# zloshnik2.net
KiCad netlist of a schematic drawn in EAGLE
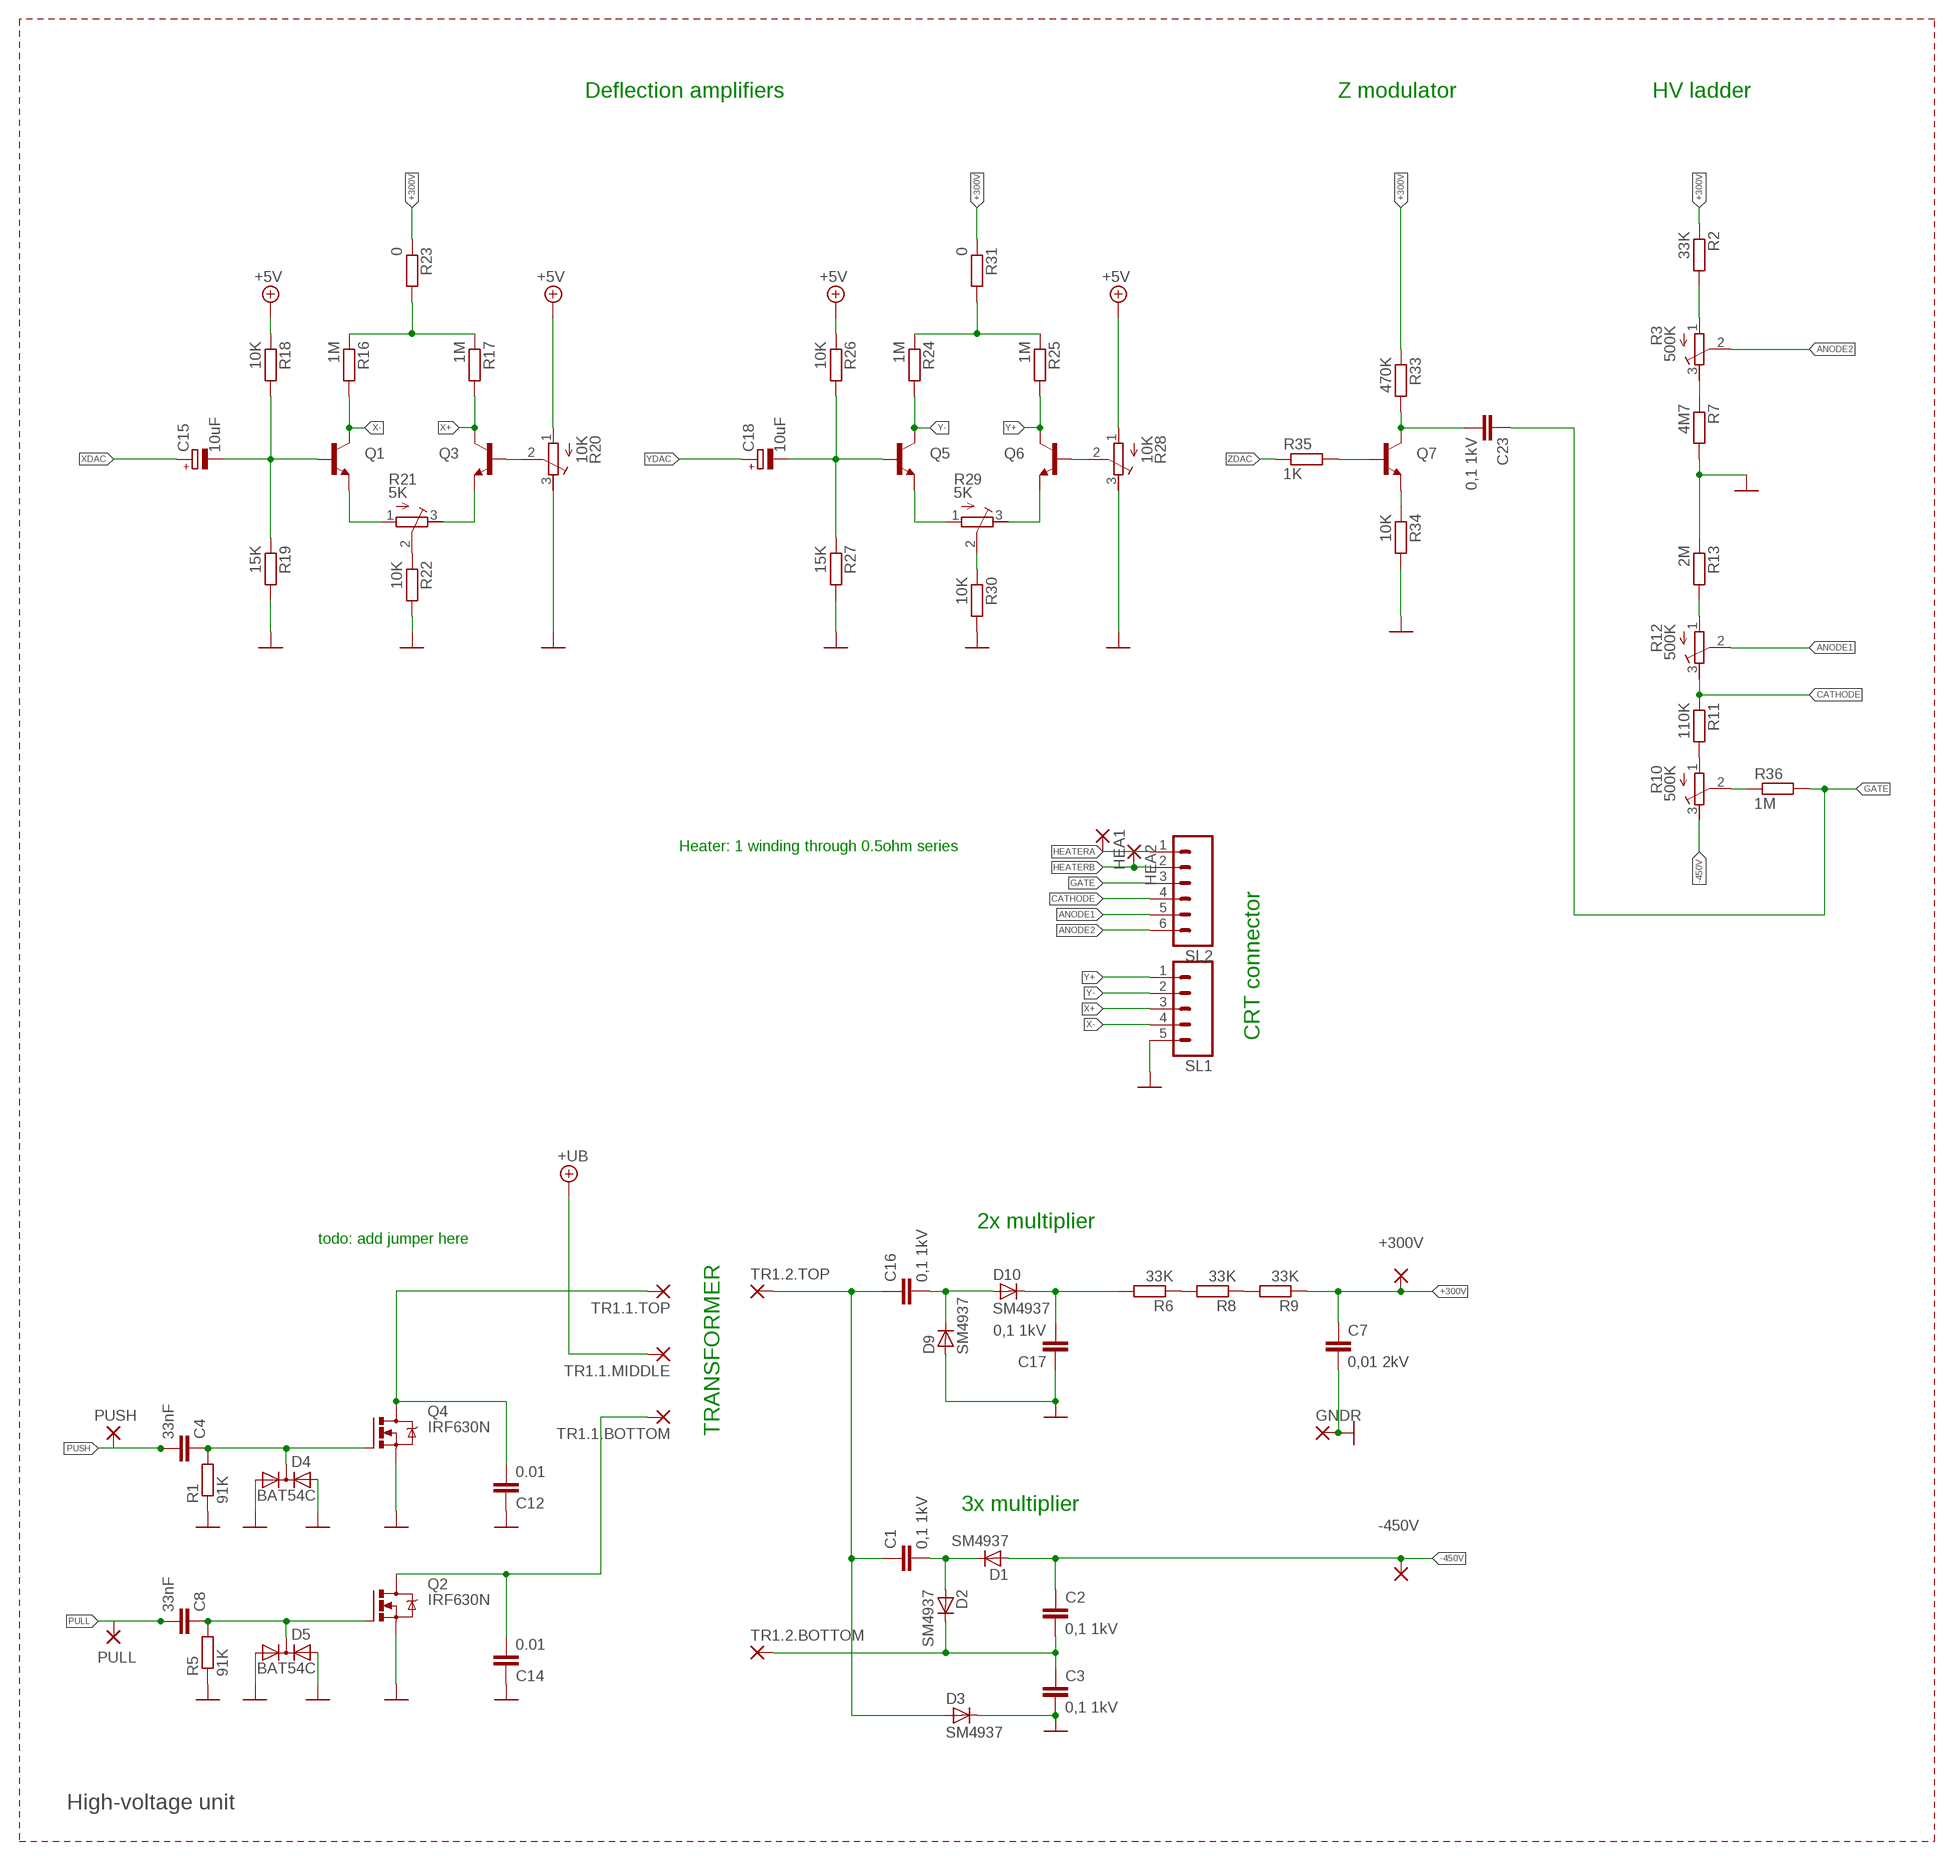
[diagram p0: schematic, sheet 1, part 1 of 2]
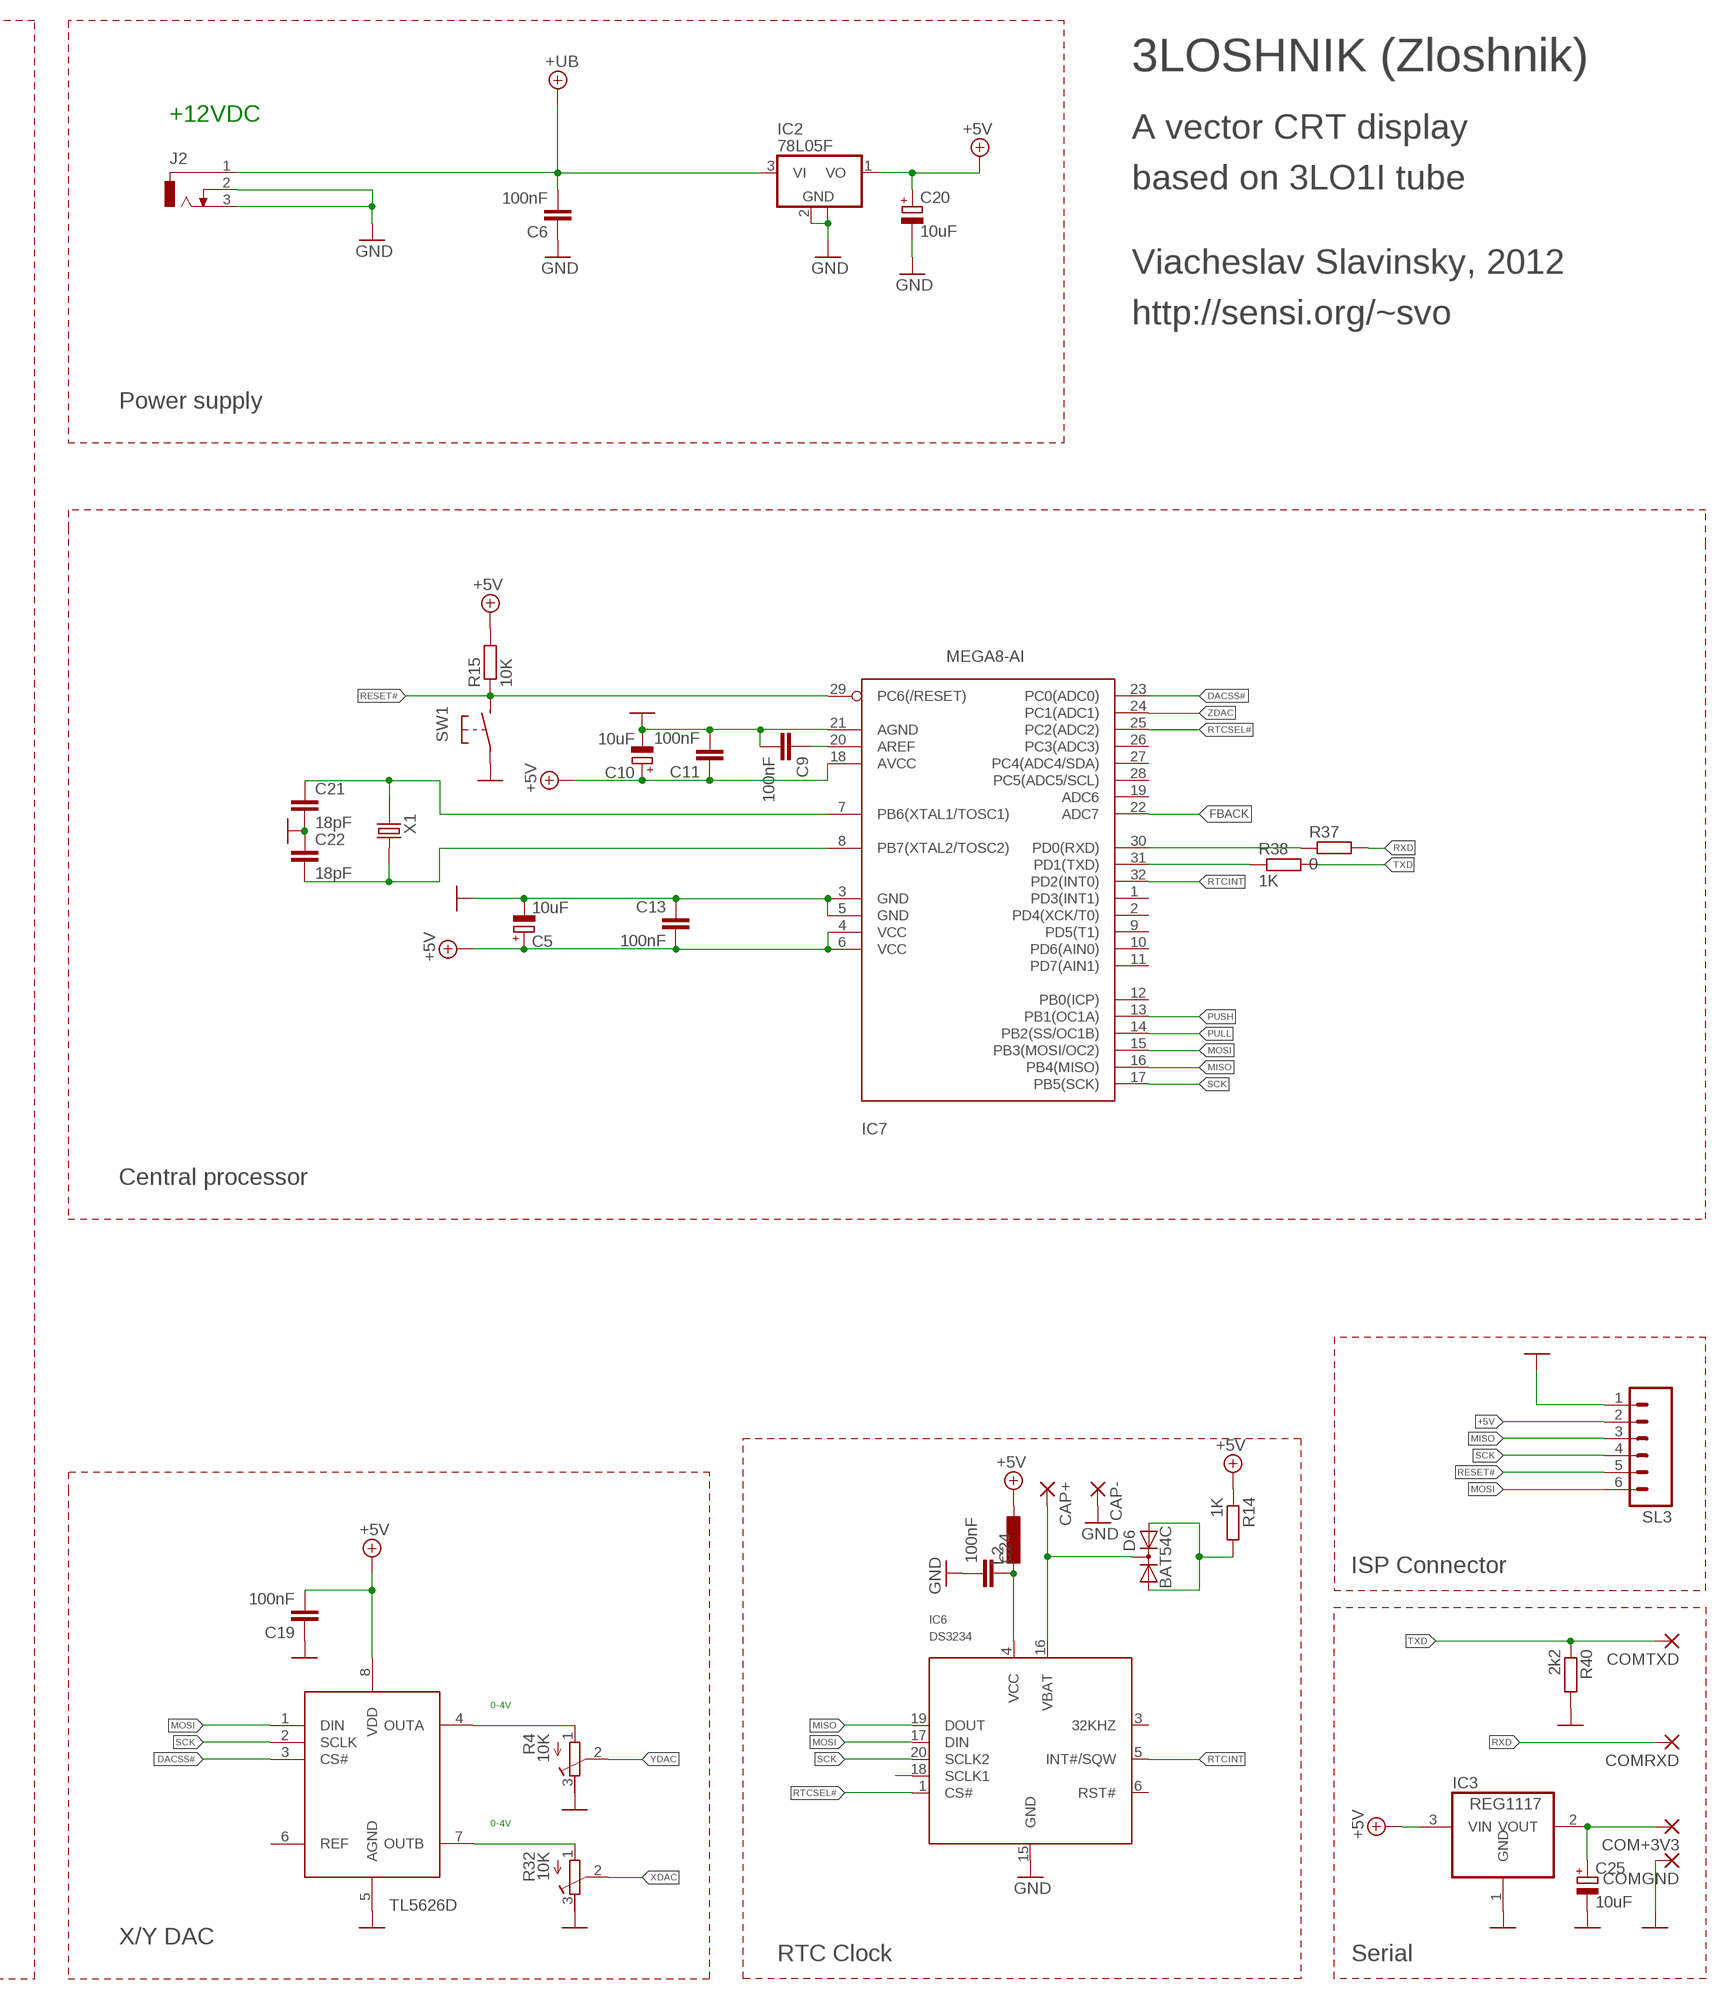
[diagram p1: schematic, sheet 1, part 2 of 2]

(export (version "E")
  (design (tool "Eeschema 10.0.6"))
  (components
    (comp (ref "+300V")
      (value "1,6/0,8")
      (footprint "eagle-import:1,6_0,8")
      (libsource (lib "eagle-import") (part "1,6/0,8"))
    )
    (comp (ref "-450V")
      (value "1,6/0,8")
      (footprint "eagle-import:1,6_0,8")
      (libsource (lib "eagle-import") (part "1,6/0,8"))
    )
    (comp (ref "C1")
      (value "0,1 1kV")
      (footprint "eagle-import:C2220K")
      (libsource (lib "eagle-import") (part "C-EUC2220K"))
    )
    (comp (ref "C2")
      (value "0,1 1kV")
      (footprint "eagle-import:C2220K")
      (libsource (lib "eagle-import") (part "C-EUC2220K"))
    )
    (comp (ref "C3")
      (value "0,1 1kV")
      (footprint "eagle-import:C2220K")
      (libsource (lib "eagle-import") (part "C-EUC2220K"))
    )
    (comp (ref "C4")
      (value "33nF")
      (footprint "eagle-import:C0805S")
      (libsource (lib "eagle-import") (part "C-EUC0805S"))
    )
    (comp (ref "C5")
      (value "10uF")
      (footprint "eagle-import:SMC_B")
      (libsource (lib "eagle-import") (part "CPOL-EUSMCB"))
    )
    (comp (ref "C6")
      (value "100nF")
      (footprint "eagle-import:C0603K")
      (libsource (lib "eagle-import") (part "rcl_C-EUC0603K"))
    )
    (comp (ref "C7")
      (value "0,01 2kV")
      (footprint "eagle-import:C1812")
      (libsource (lib "eagle-import") (part "C-EUC1812"))
    )
    (comp (ref "C8")
      (value "33nF")
      (footprint "eagle-import:C0805S")
      (libsource (lib "eagle-import") (part "C-EUC0805S"))
    )
    (comp (ref "C9")
      (value "100nF")
      (footprint "eagle-import:C0603K")
      (libsource (lib "eagle-import") (part "rcl_C-EUC0603K"))
    )
    (comp (ref "C10")
      (value "10uF")
      (footprint "eagle-import:SMC_B")
      (libsource (lib "eagle-import") (part "CPOL-EUSMCB"))
    )
    (comp (ref "C11")
      (value "100nF")
      (footprint "eagle-import:C0603K")
      (libsource (lib "eagle-import") (part "rcl_C-EUC0603K"))
    )
    (comp (ref "C12")
      (value "0.01")
      (footprint "eagle-import:C0805S")
      (libsource (lib "eagle-import") (part "C-EUC0805S"))
    )
    (comp (ref "C13")
      (value "100nF")
      (footprint "eagle-import:C0603K")
      (libsource (lib "eagle-import") (part "rcl_C-EUC0603K"))
    )
    (comp (ref "C14")
      (value "0.01")
      (footprint "eagle-import:C0805S")
      (libsource (lib "eagle-import") (part "C-EUC0805S"))
    )
    (comp (ref "C15")
      (value "10uF")
      (footprint "eagle-import:SMC_B")
      (libsource (lib "eagle-import") (part "CPOL-EUSMCB"))
    )
    (comp (ref "C16")
      (value "0,1 1kV")
      (footprint "eagle-import:C2220K")
      (libsource (lib "eagle-import") (part "C-EUC2220K"))
    )
    (comp (ref "C17")
      (value "0,1 1kV")
      (footprint "eagle-import:C2220K")
      (libsource (lib "eagle-import") (part "C-EUC2220K"))
    )
    (comp (ref "C18")
      (value "10uF")
      (footprint "eagle-import:SMC_B")
      (libsource (lib "eagle-import") (part "CPOL-EUSMCB"))
    )
    (comp (ref "C19")
      (value "100nF")
      (footprint "eagle-import:C0603K")
      (libsource (lib "eagle-import") (part "rcl_C-EUC0603K"))
    )
    (comp (ref "C20")
      (value "10uF")
      (footprint "eagle-import:SMC_B")
      (libsource (lib "eagle-import") (part "CPOL-EUSMCB"))
    )
    (comp (ref "C21")
      (value "18pF")
      (footprint "eagle-import:C0805S")
      (libsource (lib "eagle-import") (part "C-EUC0805S"))
    )
    (comp (ref "C22")
      (value "18pF")
      (footprint "eagle-import:C0805S")
      (libsource (lib "eagle-import") (part "C-EUC0805S"))
    )
    (comp (ref "C23")
      (value "0,1 1kV")
      (footprint "eagle-import:C2220K")
      (libsource (lib "eagle-import") (part "C-EUC2220K"))
    )
    (comp (ref "C24")
      (value "100nF")
      (footprint "eagle-import:C0603K")
      (libsource (lib "eagle-import") (part "rcl_C-EUC0603K"))
    )
    (comp (ref "C25")
      (value "10uF")
      (footprint "eagle-import:SMC_B")
      (libsource (lib "eagle-import") (part "CPOL-EUSMCB"))
    )
    (comp (ref "CAP+")
      (value "2,54/0,8")
      (footprint "eagle-import:2,54_0,8")
      (libsource (lib "eagle-import") (part "2,54/0,8"))
    )
    (comp (ref "CAP-")
      (value "2,54/0,8")
      (footprint "eagle-import:2,54_0,8")
      (libsource (lib "eagle-import") (part "2,54/0,8"))
    )
    (comp (ref "COM+3V3")
      (value "1,6/0,8")
      (footprint "eagle-import:1,6_0,8")
      (libsource (lib "eagle-import") (part "1,6/0,8"))
    )
    (comp (ref "COMGND")
      (value "1,6/0,8")
      (footprint "eagle-import:1,6_0,8")
      (libsource (lib "eagle-import") (part "1,6/0,8"))
    )
    (comp (ref "COMRXD")
      (value "1,6/0,8")
      (footprint "eagle-import:1,6_0,8")
      (libsource (lib "eagle-import") (part "1,6/0,8"))
    )
    (comp (ref "COMTXD")
      (value "1,6/0,8")
      (footprint "eagle-import:1,6_0,8")
      (libsource (lib "eagle-import") (part "1,6/0,8"))
    )
    (comp (ref "D1")
      (value "SM4937")
      (footprint "eagle-import:SOD87")
      (libsource (lib "eagle-import") (part "D-SOD-87"))
    )
    (comp (ref "D2")
      (value "SM4937")
      (footprint "eagle-import:SOD87")
      (libsource (lib "eagle-import") (part "D-SOD-87"))
    )
    (comp (ref "D3")
      (value "SM4937")
      (footprint "eagle-import:SOD87")
      (libsource (lib "eagle-import") (part "D-SOD-87"))
    )
    (comp (ref "D4")
      (value "BAT54C")
      (footprint "eagle-import:SOT23")
      (libsource (lib "eagle-import") (part "DIODE-2AC|CASOT23"))
    )
    (comp (ref "D5")
      (value "BAT54C")
      (footprint "eagle-import:SOT23")
      (libsource (lib "eagle-import") (part "DIODE-2AC|CASOT23"))
    )
    (comp (ref "D6")
      (value "BAT54C")
      (footprint "eagle-import:SOT23")
      (libsource (lib "eagle-import") (part "DIODE-2AC|CASOT23"))
    )
    (comp (ref "D9")
      (value "SM4937")
      (footprint "eagle-import:SOD87")
      (libsource (lib "eagle-import") (part "D-SOD-87"))
    )
    (comp (ref "D10")
      (value "SM4937")
      (footprint "eagle-import:SOD87")
      (libsource (lib "eagle-import") (part "D-SOD-87"))
    )
    (comp (ref "GNDR")
      (value "1,6/0,8")
      (footprint "eagle-import:1,6_0,8")
      (libsource (lib "eagle-import") (part "1,6/0,8"))
    )
    (comp (ref "HEA1")
      (value "1,6/0,8")
      (footprint "eagle-import:1,6_0,8")
      (libsource (lib "eagle-import") (part "1,6/0,8"))
    )
    (comp (ref "HEA2")
      (value "1,6/0,8")
      (footprint "eagle-import:1,6_0,8")
      (libsource (lib "eagle-import") (part "1,6/0,8"))
    )
    (comp (ref "IC1")
      (value "TLV5626D")
      (footprint "eagle-import:SO08")
      (libsource (lib "eagle-import") (part "TL5626D"))
    )
    (comp (ref "IC2")
      (value "78L05F")
      (footprint "eagle-import:SOT89")
      (libsource (lib "eagle-import") (part "78LF05"))
    )
    (comp (ref "IC3")
      (value "REG1117")
      (footprint "eagle-import:SOT223")
      (libsource (lib "eagle-import") (part "REG1117"))
    )
    (comp (ref "IC6")
      (value "DS3234")
      (footprint "eagle-import:SO-20DW")
      (libsource (lib "eagle-import") (part "DS3234"))
    )
    (comp (ref "IC7")
      (value "MEGA8-AI")
      (footprint "eagle-import:TQFP32-08")
      (libsource (lib "eagle-import") (part "MEGA8-AI"))
    )
    (comp (ref "J2")
      (value "DCJ-SMALL")
      (footprint "eagle-import:DCJ-SMALL")
      (libsource (lib "eagle-import") (part "DCJ-SMALL"))
    )
    (comp (ref "L2")
      (value "L-EUL3230M")
      (footprint "eagle-import:L3230M")
      (libsource (lib "eagle-import") (part "L-EUL3230M"))
    )
    (comp (ref "PULL")
      (value "1,6/0,8")
      (footprint "eagle-import:1,6_0,8")
      (libsource (lib "eagle-import") (part "1,6/0,8"))
    )
    (comp (ref "PUSH")
      (value "1,6/0,8")
      (footprint "eagle-import:1,6_0,8")
      (libsource (lib "eagle-import") (part "1,6/0,8"))
    )
    (comp (ref "Q1")
      (value "TRANSISTOR_NPNSOT23-3")
      (footprint "eagle-import:SOT23-3")
      (libsource (lib "eagle-import") (part "TRANSISTOR_NPNSOT23-3"))
    )
    (comp (ref "Q2")
      (value "IRF630N")
      (footprint "eagle-import:TO220BV")
      (libsource (lib "eagle-import") (part "IRF740"))
    )
    (comp (ref "Q3")
      (value "TRANSISTOR_NPNSOT23-3")
      (footprint "eagle-import:SOT23-3")
      (libsource (lib "eagle-import") (part "TRANSISTOR_NPNSOT23-3"))
    )
    (comp (ref "Q4")
      (value "IRF630N")
      (footprint "eagle-import:TO220BV")
      (libsource (lib "eagle-import") (part "IRF740"))
    )
    (comp (ref "Q5")
      (value "TRANSISTOR_NPNSOT23-3")
      (footprint "eagle-import:SOT23-3")
      (libsource (lib "eagle-import") (part "TRANSISTOR_NPNSOT23-3"))
    )
    (comp (ref "Q6")
      (value "TRANSISTOR_NPNSOT23-3")
      (footprint "eagle-import:SOT23-3")
      (libsource (lib "eagle-import") (part "TRANSISTOR_NPNSOT23-3"))
    )
    (comp (ref "Q7")
      (value "TRANSISTOR_NPNSOT23-3")
      (footprint "eagle-import:SOT23-3")
      (libsource (lib "eagle-import") (part "TRANSISTOR_NPNSOT23-3"))
    )
    (comp (ref "R1")
      (value "91K")
      (footprint "eagle-import:R0805-SVO")
      (libsource (lib "eagle-import") (part "R-EU_R0805S"))
    )
    (comp (ref "R2")
      (value "33K")
      (footprint "eagle-import:R0805-SVO")
      (libsource (lib "eagle-import") (part "R-EU_R0805S"))
    )
    (comp (ref "R3")
      (value "500K")
      (footprint "eagle-import:RTRIM4G_J")
      (libsource (lib "eagle-import") (part "R-TRIMM4G/J"))
    )
    (comp (ref "R4")
      (value "10K")
      (footprint "eagle-import:RTRIM4G_J")
      (libsource (lib "eagle-import") (part "R-TRIMM4G/J"))
    )
    (comp (ref "R5")
      (value "91K")
      (footprint "eagle-import:R0805-SVO")
      (libsource (lib "eagle-import") (part "R-EU_R0805S"))
    )
    (comp (ref "R6")
      (value "33K")
      (footprint "eagle-import:R0805-SVO")
      (libsource (lib "eagle-import") (part "R-EU_R0805S"))
    )
    (comp (ref "R7")
      (value "4M7")
      (footprint "eagle-import:R0805-SVO")
      (libsource (lib "eagle-import") (part "R-EU_R0805S"))
    )
    (comp (ref "R8")
      (value "33K")
      (footprint "eagle-import:R0805-SVO")
      (libsource (lib "eagle-import") (part "R-EU_R0805S"))
    )
    (comp (ref "R9")
      (value "33K")
      (footprint "eagle-import:R0805-SVO")
      (libsource (lib "eagle-import") (part "R-EU_R0805S"))
    )
    (comp (ref "R10")
      (value "500K")
      (footprint "eagle-import:RTRIM4G_J")
      (libsource (lib "eagle-import") (part "R-TRIMM4G/J"))
    )
    (comp (ref "R11")
      (value "110K")
      (footprint "eagle-import:R0805-SVO")
      (libsource (lib "eagle-import") (part "R-EU_R0805S"))
    )
    (comp (ref "R12")
      (value "500K")
      (footprint "eagle-import:RTRIM4G_J")
      (libsource (lib "eagle-import") (part "R-TRIMM4G/J"))
    )
    (comp (ref "R13")
      (value "2M")
      (footprint "eagle-import:R0805-SVO")
      (libsource (lib "eagle-import") (part "R-EU_R0805S"))
    )
    (comp (ref "R14")
      (value "1K")
      (footprint "eagle-import:R0805-SVO")
      (libsource (lib "eagle-import") (part "R-EU_R0805S"))
    )
    (comp (ref "R15")
      (value "10K")
      (footprint "eagle-import:R0805-SVO")
      (libsource (lib "eagle-import") (part "R-EU_R0805S"))
    )
    (comp (ref "R16")
      (value "1M")
      (footprint "eagle-import:R0805-SVO")
      (libsource (lib "eagle-import") (part "R-EU_R0805S"))
    )
    (comp (ref "R17")
      (value "1M")
      (footprint "eagle-import:R0805-SVO")
      (libsource (lib "eagle-import") (part "R-EU_R0805S"))
    )
    (comp (ref "R18")
      (value "10K")
      (footprint "eagle-import:R0805-SVO")
      (libsource (lib "eagle-import") (part "R-EU_R0805S"))
    )
    (comp (ref "R19")
      (value "15K")
      (footprint "eagle-import:R0805-SVO")
      (libsource (lib "eagle-import") (part "R-EU_R0805S"))
    )
    (comp (ref "R20")
      (value "10K")
      (footprint "eagle-import:RTRIM4G_J")
      (libsource (lib "eagle-import") (part "R-TRIMM4G/J"))
    )
    (comp (ref "R21")
      (value "5K")
      (footprint "eagle-import:RTRIM4G_J")
      (libsource (lib "eagle-import") (part "R-TRIMM4G/J"))
    )
    (comp (ref "R22")
      (value "10K")
      (footprint "eagle-import:R0805-SVO")
      (libsource (lib "eagle-import") (part "R-EU_R0805S"))
    )
    (comp (ref "R23")
      (value "0")
      (footprint "eagle-import:R0805-SVO")
      (libsource (lib "eagle-import") (part "R-EU_R0805S"))
    )
    (comp (ref "R24")
      (value "1M")
      (footprint "eagle-import:R0805-SVO")
      (libsource (lib "eagle-import") (part "R-EU_R0805S"))
    )
    (comp (ref "R25")
      (value "1M")
      (footprint "eagle-import:R0805-SVO")
      (libsource (lib "eagle-import") (part "R-EU_R0805S"))
    )
    (comp (ref "R26")
      (value "10K")
      (footprint "eagle-import:R0805-SVO")
      (libsource (lib "eagle-import") (part "R-EU_R0805S"))
    )
    (comp (ref "R27")
      (value "15K")
      (footprint "eagle-import:R0805-SVO")
      (libsource (lib "eagle-import") (part "R-EU_R0805S"))
    )
    (comp (ref "R28")
      (value "10K")
      (footprint "eagle-import:RTRIM4G_J")
      (libsource (lib "eagle-import") (part "R-TRIMM4G/J"))
    )
    (comp (ref "R29")
      (value "5K")
      (footprint "eagle-import:RTRIM4G_J")
      (libsource (lib "eagle-import") (part "R-TRIMM4G/J"))
    )
    (comp (ref "R30")
      (value "10K")
      (footprint "eagle-import:R0805-SVO")
      (libsource (lib "eagle-import") (part "R-EU_R0805S"))
    )
    (comp (ref "R31")
      (value "0")
      (footprint "eagle-import:R0805-SVO")
      (libsource (lib "eagle-import") (part "R-EU_R0805S"))
    )
    (comp (ref "R32")
      (value "10K")
      (footprint "eagle-import:RTRIM4G_J")
      (libsource (lib "eagle-import") (part "R-TRIMM4G/J"))
    )
    (comp (ref "R33")
      (value "470K")
      (footprint "eagle-import:R0805-SVO")
      (libsource (lib "eagle-import") (part "R-EU_R0805S"))
    )
    (comp (ref "R34")
      (value "10K")
      (footprint "eagle-import:R0805-SVO")
      (libsource (lib "eagle-import") (part "R-EU_R0805S"))
    )
    (comp (ref "R35")
      (value "1K")
      (footprint "eagle-import:R0805-SVO")
      (libsource (lib "eagle-import") (part "R-EU_R0805S"))
    )
    (comp (ref "R36")
      (value "1M")
      (footprint "eagle-import:R0805-SVO")
      (libsource (lib "eagle-import") (part "R-EU_R0805S"))
    )
    (comp (ref "R37")
      (value "0")
      (footprint "eagle-import:R0805-SVO")
      (libsource (lib "eagle-import") (part "R-EU_R0805S"))
    )
    (comp (ref "R38")
      (value "1K")
      (footprint "eagle-import:R0805-SVO")
      (libsource (lib "eagle-import") (part "R-EU_R0805S"))
    )
    (comp (ref "R40")
      (value "2k2")
      (footprint "eagle-import:R0805-SVO")
      (libsource (lib "eagle-import") (part "R-EU_R0805S"))
    )
    (comp (ref "SL1")
      (value "M05")
      (footprint "eagle-import:05P")
      (libsource (lib "eagle-import") (part "M05"))
    )
    (comp (ref "SL2")
      (value "M06")
      (footprint "eagle-import:06P")
      (libsource (lib "eagle-import") (part "M06"))
    )
    (comp (ref "SL3")
      (value "M06")
      (footprint "eagle-import:06P")
      (libsource (lib "eagle-import") (part "M06"))
    )
    (comp (ref "SW1")
      (value "BUTTON-IT_1181")
      (footprint "eagle-import:SW_IT1181")
      (libsource (lib "eagle-import") (part "BUTTON-IT_1181"))
    )
    (comp (ref "TR1.1.BOTTOM")
      (value "1,6/0,8")
      (footprint "eagle-import:1,6_0,8")
      (libsource (lib "eagle-import") (part "1,6/0,8"))
    )
    (comp (ref "TR1.1.MIDDLE")
      (value "1,6/0,8")
      (footprint "eagle-import:1,6_0,8")
      (libsource (lib "eagle-import") (part "1,6/0,8"))
    )
    (comp (ref "TR1.1.TOP")
      (value "1,6/0,8")
      (footprint "eagle-import:1,6_0,8")
      (libsource (lib "eagle-import") (part "1,6/0,8"))
    )
    (comp (ref "TR1.2.BOTTOM")
      (value "1,6/0,8")
      (footprint "eagle-import:1,6_0,8")
      (libsource (lib "eagle-import") (part "1,6/0,8"))
    )
    (comp (ref "TR1.2.TOP")
      (value "1,6/0,8")
      (footprint "eagle-import:1,6_0,8")
      (libsource (lib "eagle-import") (part "1,6/0,8"))
    )
    (comp (ref "X1")
      (value "XTAL0532")
      (footprint "eagle-import:XTAL_0532")
      (libsource (lib "eagle-import") (part "XTAL0532"))
    )
  )
  (nets
    (net (code "1") (name "+5V") (class "Default")
      (node (ref "C10") (pin "+") (pinfunction "+_+") (pintype "passive"))
      (node (ref "C11") (pin "1") (pinfunction "1_1") (pintype "passive"))
      (node (ref "C13") (pin "2") (pinfunction "2_2") (pintype "passive"))
      (node (ref "C19") (pin "2") (pinfunction "2_2") (pintype "passive"))
      (node (ref "C20") (pin "+") (pinfunction "+_+") (pintype "passive"))
      (node (ref "C5") (pin "+") (pinfunction "+_+") (pintype "passive"))
      (node (ref "IC1") (pin "8") (pinfunction "VDD_8") (pintype "power_in"))
      (node (ref "IC2") (pin "1") (pinfunction "VO_1") (pintype "passive"))
      (node (ref "IC3") (pin "3") (pinfunction "VIN_3") (pintype "input"))
      (node (ref "IC7") (pin "18") (pinfunction "AVCC_18") (pintype "power_in"))
      (node (ref "IC7") (pin "4") (pinfunction "VCC_4") (pintype "power_in"))
      (node (ref "IC7") (pin "6") (pinfunction "VCC_6") (pintype "power_in"))
      (node (ref "L2") (pin "1") (pinfunction "1_1") (pintype "passive"))
      (node (ref "R14") (pin "1") (pinfunction "1_1") (pintype "passive"))
      (node (ref "R15") (pin "2") (pinfunction "2_2") (pintype "passive"))
      (node (ref "R18") (pin "1") (pinfunction "1_1") (pintype "passive"))
      (node (ref "R20") (pin "1") (pinfunction "E_1") (pintype "passive"))
      (node (ref "R26") (pin "1") (pinfunction "1_1") (pintype "passive"))
      (node (ref "R28") (pin "1") (pinfunction "E_1") (pintype "passive"))
      (node (ref "SL3") (pin "2") (pinfunction "2_2") (pintype "passive"))
    )
    (net (code "2") (name "+300V") (class "Default")
      (node (ref "+300V") (pin "1") (pinfunction "P_1") (pintype "passive"))
      (node (ref "C7") (pin "1") (pinfunction "1_1") (pintype "passive"))
      (node (ref "R2") (pin "1") (pinfunction "1_1") (pintype "passive"))
      (node (ref "R23") (pin "1") (pinfunction "1_1") (pintype "passive"))
      (node (ref "R31") (pin "1") (pinfunction "1_1") (pintype "passive"))
      (node (ref "R33") (pin "1") (pinfunction "1_1") (pintype "passive"))
      (node (ref "R9") (pin "1") (pinfunction "1_1") (pintype "passive"))
    )
    (net (code "3") (name "+UB") (class "Default")
      (node (ref "C6") (pin "2") (pinfunction "2_2") (pintype "passive"))
      (node (ref "IC2") (pin "3") (pinfunction "VI_3") (pintype "input"))
      (node (ref "J2") (pin "1") (pinfunction "1_1") (pintype "passive"))
      (node (ref "TR1.1.MIDDLE") (pin "1") (pinfunction "P_1") (pintype "passive"))
    )
    (net (code "4") (name "-450V") (class "Default")
      (node (ref "-450V") (pin "1") (pinfunction "P_1") (pintype "passive"))
      (node (ref "C2") (pin "1") (pinfunction "1_1") (pintype "passive"))
      (node (ref "D1") (pin "2") (pinfunction "A_2") (pintype "passive"))
      (node (ref "R10") (pin "3") (pinfunction "A_3") (pintype "passive"))
    )
    (net (code "5") (name "ANODE1") (class "Default")
      (node (ref "R12") (pin "2") (pinfunction "S_2") (pintype "passive"))
      (node (ref "SL2") (pin "5") (pinfunction "5_5") (pintype "passive"))
    )
    (net (code "6") (name "ANODE2") (class "Default")
      (node (ref "R3") (pin "2") (pinfunction "S_2") (pintype "passive"))
      (node (ref "SL2") (pin "6") (pinfunction "6_6") (pintype "passive"))
    )
    (net (code "7") (name "CATHODE") (class "Default")
      (node (ref "R11") (pin "1") (pinfunction "1_1") (pintype "passive"))
      (node (ref "R12") (pin "3") (pinfunction "A_3") (pintype "passive"))
      (node (ref "SL2") (pin "4") (pinfunction "4_4") (pintype "passive"))
    )
    (net (code "8") (name "DACSS#") (class "Default")
      (node (ref "IC1") (pin "3") (pinfunction "CS#_3") (pintype "bidirectional"))
      (node (ref "IC7") (pin "23") (pinfunction "PC0(ADC0)_23") (pintype "bidirectional"))
    )
    (net (code "9") (name "FBACK") (class "Default")
      (node (ref "IC7") (pin "22") (pinfunction "ADC7_22") (pintype "bidirectional"))
    )
    (net (code "10") (name "GATE") (class "Default")
      (node (ref "C23") (pin "1") (pinfunction "1_1") (pintype "passive"))
      (node (ref "R36") (pin "2") (pinfunction "2_2") (pintype "passive"))
      (node (ref "SL2") (pin "3") (pinfunction "3_3") (pintype "passive"))
    )
    (net (code "11") (name "GND") (class "Default")
      (node (ref "C10") (pin "-") (pinfunction "-_-") (pintype "passive"))
      (node (ref "C11") (pin "2") (pinfunction "2_2") (pintype "passive"))
      (node (ref "C12") (pin "1") (pinfunction "1_1") (pintype "passive"))
      (node (ref "C13") (pin "1") (pinfunction "1_1") (pintype "passive"))
      (node (ref "C14") (pin "1") (pinfunction "1_1") (pintype "passive"))
      (node (ref "C17") (pin "1") (pinfunction "1_1") (pintype "passive"))
      (node (ref "C19") (pin "1") (pinfunction "1_1") (pintype "passive"))
      (node (ref "C20") (pin "-") (pinfunction "-_-") (pintype "passive"))
      (node (ref "C21") (pin "2") (pinfunction "2_2") (pintype "passive"))
      (node (ref "C22") (pin "1") (pinfunction "1_1") (pintype "passive"))
      (node (ref "C24") (pin "2") (pinfunction "2_2") (pintype "passive"))
      (node (ref "C25") (pin "-") (pinfunction "-_-") (pintype "passive"))
      (node (ref "C3") (pin "2") (pinfunction "2_2") (pintype "passive"))
      (node (ref "C5") (pin "-") (pinfunction "-_-") (pintype "passive"))
      (node (ref "C6") (pin "1") (pinfunction "1_1") (pintype "passive"))
      (node (ref "C7") (pin "2") (pinfunction "2_2") (pintype "passive"))
      (node (ref "C9") (pin "2") (pinfunction "2_2") (pintype "passive"))
      (node (ref "CAP-") (pin "1") (pinfunction "P_1") (pintype "passive"))
      (node (ref "COMGND") (pin "1") (pinfunction "P_1") (pintype "passive"))
      (node (ref "D3") (pin "1") (pinfunction "C_1") (pintype "passive"))
      (node (ref "D4") (pin "1") (pinfunction "A1_1") (pintype "passive"))
      (node (ref "D4") (pin "2") (pinfunction "A2_2") (pintype "passive"))
      (node (ref "D5") (pin "1") (pinfunction "A1_1") (pintype "passive"))
      (node (ref "D5") (pin "2") (pinfunction "A2_2") (pintype "passive"))
      (node (ref "D9") (pin "2") (pinfunction "A_2") (pintype "passive"))
      (node (ref "GNDR") (pin "1") (pinfunction "P_1") (pintype "passive"))
      (node (ref "IC1") (pin "5") (pinfunction "AGND_5") (pintype "power_in"))
      (node (ref "IC2") (pin "2") (pinfunction "GND_2") (pintype "passive"))
      (node (ref "IC2") (pin "2@1") (pinfunction "GND_2@1") (pintype "passive"))
      (node (ref "IC3") (pin "1") (pinfunction "GND_1") (pintype "power_in"))
      (node (ref "IC6") (pin "15") (pinfunction "GND_15") (pintype "bidirectional"))
      (node (ref "IC7") (pin "21") (pinfunction "AGND_21") (pintype "power_in"))
      (node (ref "IC7") (pin "3") (pinfunction "GND_3") (pintype "power_in"))
      (node (ref "IC7") (pin "5") (pinfunction "GND_5") (pintype "power_in"))
      (node (ref "J2") (pin "2") (pinfunction "2_2") (pintype "passive"))
      (node (ref "J2") (pin "3") (pinfunction "3_3") (pintype "passive"))
      (node (ref "Q2") (pin "S") (pinfunction "S_S") (pintype "passive"))
      (node (ref "Q4") (pin "S") (pinfunction "S_S") (pintype "passive"))
      (node (ref "R1") (pin "1") (pinfunction "1_1") (pintype "passive"))
      (node (ref "R13") (pin "1") (pinfunction "1_1") (pintype "passive"))
      (node (ref "R19") (pin "2") (pinfunction "2_2") (pintype "passive"))
      (node (ref "R20") (pin "3") (pinfunction "A_3") (pintype "passive"))
      (node (ref "R22") (pin "2") (pinfunction "2_2") (pintype "passive"))
      (node (ref "R27") (pin "2") (pinfunction "2_2") (pintype "passive"))
      (node (ref "R28") (pin "3") (pinfunction "A_3") (pintype "passive"))
      (node (ref "R30") (pin "2") (pinfunction "2_2") (pintype "passive"))
      (node (ref "R32") (pin "3") (pinfunction "A_3") (pintype "passive"))
      (node (ref "R34") (pin "2") (pinfunction "2_2") (pintype "passive"))
      (node (ref "R4") (pin "3") (pinfunction "A_3") (pintype "passive"))
      (node (ref "R40") (pin "2") (pinfunction "2_2") (pintype "passive"))
      (node (ref "R5") (pin "1") (pinfunction "1_1") (pintype "passive"))
      (node (ref "R7") (pin "2") (pinfunction "2_2") (pintype "passive"))
      (node (ref "SL1") (pin "5") (pinfunction "5_5") (pintype "passive"))
      (node (ref "SL3") (pin "1") (pinfunction "1_1") (pintype "passive"))
      (node (ref "SW1") (pin "P$1") (pinfunction "P1_P$1") (pintype "passive"))
    )
    (net (code "12") (name "HEATERA") (class "Default")
      (node (ref "HEA1") (pin "1") (pinfunction "P_1") (pintype "passive"))
      (node (ref "SL2") (pin "1") (pinfunction "1_1") (pintype "passive"))
    )
    (net (code "13") (name "HEATERB") (class "Default")
      (node (ref "HEA2") (pin "1") (pinfunction "P_1") (pintype "passive"))
      (node (ref "SL2") (pin "2") (pinfunction "2_2") (pintype "passive"))
    )
    (net (code "14") (name "MISO") (class "Default")
      (node (ref "IC6") (pin "19") (pinfunction "DOUT_19") (pintype "bidirectional"))
      (node (ref "IC7") (pin "16") (pinfunction "PB4(MISO)_16") (pintype "bidirectional"))
      (node (ref "SL3") (pin "3") (pinfunction "3_3") (pintype "passive"))
    )
    (net (code "15") (name "MOSI") (class "Default")
      (node (ref "IC1") (pin "1") (pinfunction "DIN_1") (pintype "bidirectional"))
      (node (ref "IC6") (pin "17") (pinfunction "DIN_17") (pintype "bidirectional"))
      (node (ref "IC7") (pin "15") (pinfunction "PB3(MOSI/OC2)_15") (pintype "bidirectional"))
      (node (ref "SL3") (pin "6") (pinfunction "6_6") (pintype "passive"))
    )
    (net (code "16") (name "Net-(CAP+-P)") (class "Default")
      (node (ref "CAP+") (pin "1") (pinfunction "P_1") (pintype "passive"))
      (node (ref "D6") (pin "3") (pinfunction "C_3") (pintype "passive"))
      (node (ref "IC6") (pin "16") (pinfunction "VBAT_16") (pintype "bidirectional"))
    )
    (net (code "17") (name "Net-(COM+3V3-P)") (class "Default")
      (node (ref "C25") (pin "+") (pinfunction "+_+") (pintype "passive"))
      (node (ref "COM+3V3") (pin "1") (pinfunction "P_1") (pintype "passive"))
      (node (ref "IC3") (pin "2") (pinfunction "VOUT_2") (pintype "output"))
    )
    (net (code "18") (name "Net-(D1-C)") (class "Default")
      (node (ref "C1") (pin "2") (pinfunction "2_2") (pintype "passive"))
      (node (ref "D1") (pin "1") (pinfunction "C_1") (pintype "passive"))
      (node (ref "D2") (pin "2") (pinfunction "A_2") (pintype "passive"))
    )
    (net (code "19") (name "Net-(D2-C)") (class "Default")
      (node (ref "C2") (pin "2") (pinfunction "2_2") (pintype "passive"))
      (node (ref "C3") (pin "1") (pinfunction "1_1") (pintype "passive"))
      (node (ref "D2") (pin "1") (pinfunction "C_1") (pintype "passive"))
      (node (ref "TR1.2.BOTTOM") (pin "1") (pinfunction "P_1") (pintype "passive"))
    )
    (net (code "20") (name "Net-(D3-A)") (class "Default")
      (node (ref "C1") (pin "1") (pinfunction "1_1") (pintype "passive"))
      (node (ref "C16") (pin "1") (pinfunction "1_1") (pintype "passive"))
      (node (ref "D3") (pin "2") (pinfunction "A_2") (pintype "passive"))
      (node (ref "TR1.2.TOP") (pin "1") (pinfunction "P_1") (pintype "passive"))
    )
    (net (code "21") (name "Net-(D4-C)") (class "Default")
      (node (ref "C4") (pin "1") (pinfunction "1_1") (pintype "passive"))
      (node (ref "D4") (pin "3") (pinfunction "C_3") (pintype "passive"))
      (node (ref "Q4") (pin "G") (pinfunction "G_G") (pintype "passive"))
      (node (ref "R1") (pin "2") (pinfunction "2_2") (pintype "passive"))
    )
    (net (code "22") (name "Net-(D5-C)") (class "Default")
      (node (ref "C8") (pin "1") (pinfunction "1_1") (pintype "passive"))
      (node (ref "D5") (pin "3") (pinfunction "C_3") (pintype "passive"))
      (node (ref "Q2") (pin "G") (pinfunction "G_G") (pintype "passive"))
      (node (ref "R5") (pin "2") (pinfunction "2_2") (pintype "passive"))
    )
    (net (code "23") (name "Net-(D6-A1)") (class "Default")
      (node (ref "D6") (pin "1") (pinfunction "A1_1") (pintype "passive"))
      (node (ref "D6") (pin "2") (pinfunction "A2_2") (pintype "passive"))
      (node (ref "R14") (pin "2") (pinfunction "2_2") (pintype "passive"))
    )
    (net (code "24") (name "Net-(D10-A)") (class "Default")
      (node (ref "C16") (pin "2") (pinfunction "2_2") (pintype "passive"))
      (node (ref "D10") (pin "2") (pinfunction "A_2") (pintype "passive"))
      (node (ref "D9") (pin "1") (pinfunction "C_1") (pintype "passive"))
    )
    (net (code "25") (name "Net-(D10-C)") (class "Default")
      (node (ref "C17") (pin "2") (pinfunction "2_2") (pintype "passive"))
      (node (ref "D10") (pin "1") (pinfunction "C_1") (pintype "passive"))
      (node (ref "R6") (pin "2") (pinfunction "2_2") (pintype "passive"))
    )
    (net (code "26") (name "Net-(IC1-OUTA)") (class "Default")
      (node (ref "IC1") (pin "4") (pinfunction "OUTA_4") (pintype "bidirectional"))
      (node (ref "R4") (pin "1") (pinfunction "E_1") (pintype "passive"))
    )
    (net (code "27") (name "Net-(IC1-OUTB)") (class "Default")
      (node (ref "IC1") (pin "7") (pinfunction "OUTB_7") (pintype "bidirectional"))
      (node (ref "R32") (pin "1") (pinfunction "E_1") (pintype "passive"))
    )
    (net (code "28") (name "Net-(IC6-VCC)") (class "Default")
      (node (ref "C24") (pin "1") (pinfunction "1_1") (pintype "passive"))
      (node (ref "IC6") (pin "4") (pinfunction "VCC_4") (pintype "bidirectional"))
      (node (ref "L2") (pin "2") (pinfunction "2_2") (pintype "passive"))
    )
    (net (code "29") (name "Net-(IC7-AREF)") (class "Default")
      (node (ref "C9") (pin "1") (pinfunction "1_1") (pintype "passive"))
      (node (ref "IC7") (pin "20") (pinfunction "AREF_20") (pintype "passive"))
    )
    (net (code "30") (name "Net-(IC7-PB6(XTAL1{slash}TOSC1))") (class "Default")
      (node (ref "C21") (pin "1") (pinfunction "1_1") (pintype "passive"))
      (node (ref "IC7") (pin "7") (pinfunction "PB6(XTAL1/TOSC1)_7") (pintype "bidirectional"))
      (node (ref "X1") (pin "2") (pinfunction "1_2") (pintype "passive"))
    )
    (net (code "31") (name "Net-(IC7-PB7(XTAL2{slash}TOSC2))") (class "Default")
      (node (ref "C22") (pin "2") (pinfunction "2_2") (pintype "passive"))
      (node (ref "IC7") (pin "8") (pinfunction "PB7(XTAL2/TOSC2)_8") (pintype "bidirectional"))
      (node (ref "X1") (pin "4") (pinfunction "2_4") (pintype "passive"))
    )
    (net (code "32") (name "Net-(IC7-PD0(RXD))") (class "Default")
      (node (ref "IC7") (pin "30") (pinfunction "PD0(RXD)_30") (pintype "bidirectional"))
      (node (ref "R37") (pin "1") (pinfunction "1_1") (pintype "passive"))
    )
    (net (code "33") (name "Net-(IC7-PD1(TXD))") (class "Default")
      (node (ref "IC7") (pin "31") (pinfunction "PD1(TXD)_31") (pintype "bidirectional"))
      (node (ref "R38") (pin "1") (pinfunction "1_1") (pintype "passive"))
    )
    (net (code "34") (name "Net-(Q1-B)") (class "Default")
      (node (ref "C15") (pin "-") (pinfunction "-_-") (pintype "passive"))
      (node (ref "Q1") (pin "1") (pinfunction "B_1") (pintype "passive"))
      (node (ref "R18") (pin "2") (pinfunction "2_2") (pintype "passive"))
      (node (ref "R19") (pin "1") (pinfunction "1_1") (pintype "passive"))
    )
    (net (code "35") (name "Net-(Q1-E)") (class "Default")
      (node (ref "Q1") (pin "2") (pinfunction "E_2") (pintype "passive"))
      (node (ref "R21") (pin "1") (pinfunction "E_1") (pintype "passive"))
    )
    (net (code "36") (name "Net-(Q3-B)") (class "Default")
      (node (ref "Q3") (pin "1") (pinfunction "B_1") (pintype "passive"))
      (node (ref "R20") (pin "2") (pinfunction "S_2") (pintype "passive"))
    )
    (net (code "37") (name "Net-(Q3-E)") (class "Default")
      (node (ref "Q3") (pin "2") (pinfunction "E_2") (pintype "passive"))
      (node (ref "R21") (pin "3") (pinfunction "A_3") (pintype "passive"))
    )
    (net (code "38") (name "Net-(Q5-B)") (class "Default")
      (node (ref "C18") (pin "-") (pinfunction "-_-") (pintype "passive"))
      (node (ref "Q5") (pin "1") (pinfunction "B_1") (pintype "passive"))
      (node (ref "R26") (pin "2") (pinfunction "2_2") (pintype "passive"))
      (node (ref "R27") (pin "1") (pinfunction "1_1") (pintype "passive"))
    )
    (net (code "39") (name "Net-(Q5-E)") (class "Default")
      (node (ref "Q5") (pin "2") (pinfunction "E_2") (pintype "passive"))
      (node (ref "R29") (pin "1") (pinfunction "E_1") (pintype "passive"))
    )
    (net (code "40") (name "Net-(Q6-B)") (class "Default")
      (node (ref "Q6") (pin "1") (pinfunction "B_1") (pintype "passive"))
      (node (ref "R28") (pin "2") (pinfunction "S_2") (pintype "passive"))
    )
    (net (code "41") (name "Net-(Q6-E)") (class "Default")
      (node (ref "Q6") (pin "2") (pinfunction "E_2") (pintype "passive"))
      (node (ref "R29") (pin "3") (pinfunction "A_3") (pintype "passive"))
    )
    (net (code "42") (name "Net-(Q7-B)") (class "Default")
      (node (ref "Q7") (pin "1") (pinfunction "B_1") (pintype "passive"))
      (node (ref "R35") (pin "2") (pinfunction "2_2") (pintype "passive"))
    )
    (net (code "43") (name "Net-(Q7-C)") (class "Default")
      (node (ref "C23") (pin "2") (pinfunction "2_2") (pintype "passive"))
      (node (ref "Q7") (pin "3") (pinfunction "C_3") (pintype "passive"))
      (node (ref "R33") (pin "2") (pinfunction "2_2") (pintype "passive"))
    )
    (net (code "44") (name "Net-(Q7-E)") (class "Default")
      (node (ref "Q7") (pin "2") (pinfunction "E_2") (pintype "passive"))
      (node (ref "R34") (pin "1") (pinfunction "1_1") (pintype "passive"))
    )
    (net (code "45") (name "Net-(R3-A)") (class "Default")
      (node (ref "R3") (pin "3") (pinfunction "A_3") (pintype "passive"))
      (node (ref "R7") (pin "1") (pinfunction "1_1") (pintype "passive"))
    )
    (net (code "46") (name "Net-(R3-E)") (class "Default")
      (node (ref "R2") (pin "2") (pinfunction "2_2") (pintype "passive"))
      (node (ref "R3") (pin "1") (pinfunction "E_1") (pintype "passive"))
    )
    (net (code "47") (name "Net-(R6-Pad1)") (class "Default")
      (node (ref "R6") (pin "1") (pinfunction "1_1") (pintype "passive"))
      (node (ref "R8") (pin "2") (pinfunction "2_2") (pintype "passive"))
    )
    (net (code "48") (name "Net-(R8-Pad1)") (class "Default")
      (node (ref "R8") (pin "1") (pinfunction "1_1") (pintype "passive"))
      (node (ref "R9") (pin "2") (pinfunction "2_2") (pintype "passive"))
    )
    (net (code "49") (name "Net-(R10-E)") (class "Default")
      (node (ref "R10") (pin "1") (pinfunction "E_1") (pintype "passive"))
      (node (ref "R11") (pin "2") (pinfunction "2_2") (pintype "passive"))
    )
    (net (code "50") (name "Net-(R10-S)") (class "Default")
      (node (ref "R10") (pin "2") (pinfunction "S_2") (pintype "passive"))
      (node (ref "R36") (pin "1") (pinfunction "1_1") (pintype "passive"))
    )
    (net (code "51") (name "Net-(R12-E)") (class "Default")
      (node (ref "R12") (pin "1") (pinfunction "E_1") (pintype "passive"))
      (node (ref "R13") (pin "2") (pinfunction "2_2") (pintype "passive"))
    )
    (net (code "52") (name "Net-(R16-Pad1)") (class "Default")
      (node (ref "R16") (pin "1") (pinfunction "1_1") (pintype "passive"))
      (node (ref "R17") (pin "1") (pinfunction "1_1") (pintype "passive"))
      (node (ref "R23") (pin "2") (pinfunction "2_2") (pintype "passive"))
    )
    (net (code "53") (name "Net-(R21-S)") (class "Default")
      (node (ref "R21") (pin "2") (pinfunction "S_2") (pintype "passive"))
      (node (ref "R22") (pin "1") (pinfunction "1_1") (pintype "passive"))
    )
    (net (code "54") (name "Net-(R24-Pad1)") (class "Default")
      (node (ref "R24") (pin "1") (pinfunction "1_1") (pintype "passive"))
      (node (ref "R25") (pin "1") (pinfunction "1_1") (pintype "passive"))
      (node (ref "R31") (pin "2") (pinfunction "2_2") (pintype "passive"))
    )
    (net (code "55") (name "Net-(R29-S)") (class "Default")
      (node (ref "R29") (pin "2") (pinfunction "S_2") (pintype "passive"))
      (node (ref "R30") (pin "1") (pinfunction "1_1") (pintype "passive"))
    )
    (net (code "56") (name "Net-(TR1.1.BOTTOM-P)") (class "Default")
      (node (ref "C14") (pin "2") (pinfunction "2_2") (pintype "passive"))
      (node (ref "Q2") (pin "D") (pinfunction "D_D") (pintype "passive"))
      (node (ref "TR1.1.BOTTOM") (pin "1") (pinfunction "P_1") (pintype "passive"))
    )
    (net (code "57") (name "Net-(TR1.1.TOP-P)") (class "Default")
      (node (ref "C12") (pin "2") (pinfunction "2_2") (pintype "passive"))
      (node (ref "Q4") (pin "D") (pinfunction "D_D") (pintype "passive"))
      (node (ref "TR1.1.TOP") (pin "1") (pinfunction "P_1") (pintype "passive"))
    )
    (net (code "58") (name "PULL") (class "Default")
      (node (ref "C8") (pin "2") (pinfunction "2_2") (pintype "passive"))
      (node (ref "IC7") (pin "14") (pinfunction "PB2(SS/OC1B)_14") (pintype "bidirectional"))
      (node (ref "PULL") (pin "1") (pinfunction "P_1") (pintype "passive"))
    )
    (net (code "59") (name "PUSH") (class "Default")
      (node (ref "C4") (pin "2") (pinfunction "2_2") (pintype "passive"))
      (node (ref "IC7") (pin "13") (pinfunction "PB1(OC1A)_13") (pintype "bidirectional"))
      (node (ref "PUSH") (pin "1") (pinfunction "P_1") (pintype "passive"))
    )
    (net (code "60") (name "RESET#") (class "Default")
      (node (ref "IC7") (pin "29") (pinfunction "PC6(/RESET)_29") (pintype "bidirectional"))
      (node (ref "R15") (pin "1") (pinfunction "1_1") (pintype "passive"))
      (node (ref "SL3") (pin "5") (pinfunction "5_5") (pintype "passive"))
      (node (ref "SW1") (pin "P$2") (pinfunction "P2_P$2") (pintype "passive"))
    )
    (net (code "61") (name "RTCINT") (class "Default")
      (node (ref "IC6") (pin "5") (pinfunction "INT#/SQW_5") (pintype "bidirectional"))
      (node (ref "IC7") (pin "32") (pinfunction "PD2(INT0)_32") (pintype "bidirectional"))
    )
    (net (code "62") (name "RTCSEL#") (class "Default")
      (node (ref "IC6") (pin "1") (pinfunction "CS#_1") (pintype "bidirectional"))
      (node (ref "IC7") (pin "25") (pinfunction "PC2(ADC2)_25") (pintype "bidirectional"))
    )
    (net (code "63") (name "RXD") (class "Default")
      (node (ref "COMRXD") (pin "1") (pinfunction "P_1") (pintype "passive"))
      (node (ref "R37") (pin "2") (pinfunction "2_2") (pintype "passive"))
    )
    (net (code "64") (name "SCK") (class "Default")
      (node (ref "IC1") (pin "2") (pinfunction "SCLK_2") (pintype "bidirectional"))
      (node (ref "IC6") (pin "20") (pinfunction "SCLK2_20") (pintype "bidirectional"))
      (node (ref "IC7") (pin "17") (pinfunction "PB5(SCK)_17") (pintype "bidirectional"))
      (node (ref "SL3") (pin "4") (pinfunction "4_4") (pintype "passive"))
    )
    (net (code "65") (name "TXD") (class "Default")
      (node (ref "COMTXD") (pin "1") (pinfunction "P_1") (pintype "passive"))
      (node (ref "R38") (pin "2") (pinfunction "2_2") (pintype "passive"))
      (node (ref "R40") (pin "1") (pinfunction "1_1") (pintype "passive"))
    )
    (net (code "66") (name "X+") (class "Default")
      (node (ref "Q3") (pin "3") (pinfunction "C_3") (pintype "passive"))
      (node (ref "R17") (pin "2") (pinfunction "2_2") (pintype "passive"))
      (node (ref "SL1") (pin "3") (pinfunction "3_3") (pintype "passive"))
    )
    (net (code "67") (name "X-") (class "Default")
      (node (ref "Q1") (pin "3") (pinfunction "C_3") (pintype "passive"))
      (node (ref "R16") (pin "2") (pinfunction "2_2") (pintype "passive"))
      (node (ref "SL1") (pin "4") (pinfunction "4_4") (pintype "passive"))
    )
    (net (code "68") (name "XDAC") (class "Default")
      (node (ref "C15") (pin "+") (pinfunction "+_+") (pintype "passive"))
      (node (ref "R32") (pin "2") (pinfunction "S_2") (pintype "passive"))
    )
    (net (code "69") (name "Y+") (class "Default")
      (node (ref "Q6") (pin "3") (pinfunction "C_3") (pintype "passive"))
      (node (ref "R25") (pin "2") (pinfunction "2_2") (pintype "passive"))
      (node (ref "SL1") (pin "1") (pinfunction "1_1") (pintype "passive"))
    )
    (net (code "70") (name "Y-") (class "Default")
      (node (ref "Q5") (pin "3") (pinfunction "C_3") (pintype "passive"))
      (node (ref "R24") (pin "2") (pinfunction "2_2") (pintype "passive"))
      (node (ref "SL1") (pin "2") (pinfunction "2_2") (pintype "passive"))
    )
    (net (code "71") (name "YDAC") (class "Default")
      (node (ref "C18") (pin "+") (pinfunction "+_+") (pintype "passive"))
      (node (ref "R4") (pin "2") (pinfunction "S_2") (pintype "passive"))
    )
    (net (code "72") (name "ZDAC") (class "Default")
      (node (ref "IC7") (pin "24") (pinfunction "PC1(ADC1)_24") (pintype "bidirectional"))
      (node (ref "R35") (pin "1") (pinfunction "1_1") (pintype "passive"))
    )
    (net (code "73") (name "unconnected-(IC1-REF-Pad6)") (class "Default")
      (node (ref "IC1") (pin "6") (pinfunction "REF_6") (pintype "bidirectional"))
    )
    (net (code "74") (name "unconnected-(IC6-32KHZ-Pad3)") (class "Default")
      (node (ref "IC6") (pin "3") (pinfunction "32KHZ_3") (pintype "bidirectional"))
    )
    (net (code "75") (name "unconnected-(IC6-RST#-Pad6)") (class "Default")
      (node (ref "IC6") (pin "6") (pinfunction "RST#_6") (pintype "bidirectional"))
    )
    (net (code "76") (name "unconnected-(IC6-SCLK1-Pad18)") (class "Default")
      (node (ref "IC6") (pin "18") (pinfunction "SCLK1_18") (pintype "bidirectional"))
    )
    (net (code "77") (name "unconnected-(IC7-ADC6-Pad19)") (class "Default")
      (node (ref "IC7") (pin "19") (pinfunction "ADC6_19") (pintype "bidirectional"))
    )
    (net (code "78") (name "unconnected-(IC7-PB0(ICP)-Pad12)") (class "Default")
      (node (ref "IC7") (pin "12") (pinfunction "PB0(ICP)_12") (pintype "bidirectional"))
    )
    (net (code "79") (name "unconnected-(IC7-PC3(ADC3)-Pad26)") (class "Default")
      (node (ref "IC7") (pin "26") (pinfunction "PC3(ADC3)_26") (pintype "bidirectional"))
    )
    (net (code "80") (name "unconnected-(IC7-PC4(ADC4{slash}SDA)-Pad27)") (class "Default")
      (node (ref "IC7") (pin "27") (pinfunction "PC4(ADC4/SDA)_27") (pintype "bidirectional"))
    )
    (net (code "81") (name "unconnected-(IC7-PC5(ADC5{slash}SCL)-Pad28)") (class "Default")
      (node (ref "IC7") (pin "28") (pinfunction "PC5(ADC5/SCL)_28") (pintype "bidirectional"))
    )
    (net (code "82") (name "unconnected-(IC7-PD3(INT1)-Pad1)") (class "Default")
      (node (ref "IC7") (pin "1") (pinfunction "PD3(INT1)_1") (pintype "bidirectional"))
    )
    (net (code "83") (name "unconnected-(IC7-PD4(XCK{slash}T0)-Pad2)") (class "Default")
      (node (ref "IC7") (pin "2") (pinfunction "PD4(XCK/T0)_2") (pintype "bidirectional"))
    )
    (net (code "84") (name "unconnected-(IC7-PD5(T1)-Pad9)") (class "Default")
      (node (ref "IC7") (pin "9") (pinfunction "PD5(T1)_9") (pintype "bidirectional"))
    )
    (net (code "85") (name "unconnected-(IC7-PD6(AIN0)-Pad10)") (class "Default")
      (node (ref "IC7") (pin "10") (pinfunction "PD6(AIN0)_10") (pintype "bidirectional"))
    )
    (net (code "86") (name "unconnected-(IC7-PD7(AIN1)-Pad11)") (class "Default")
      (node (ref "IC7") (pin "11") (pinfunction "PD7(AIN1)_11") (pintype "bidirectional"))
    )
  )
)
